# AdderRev1.net
KiCad netlist of a schematic drawn in EAGLE
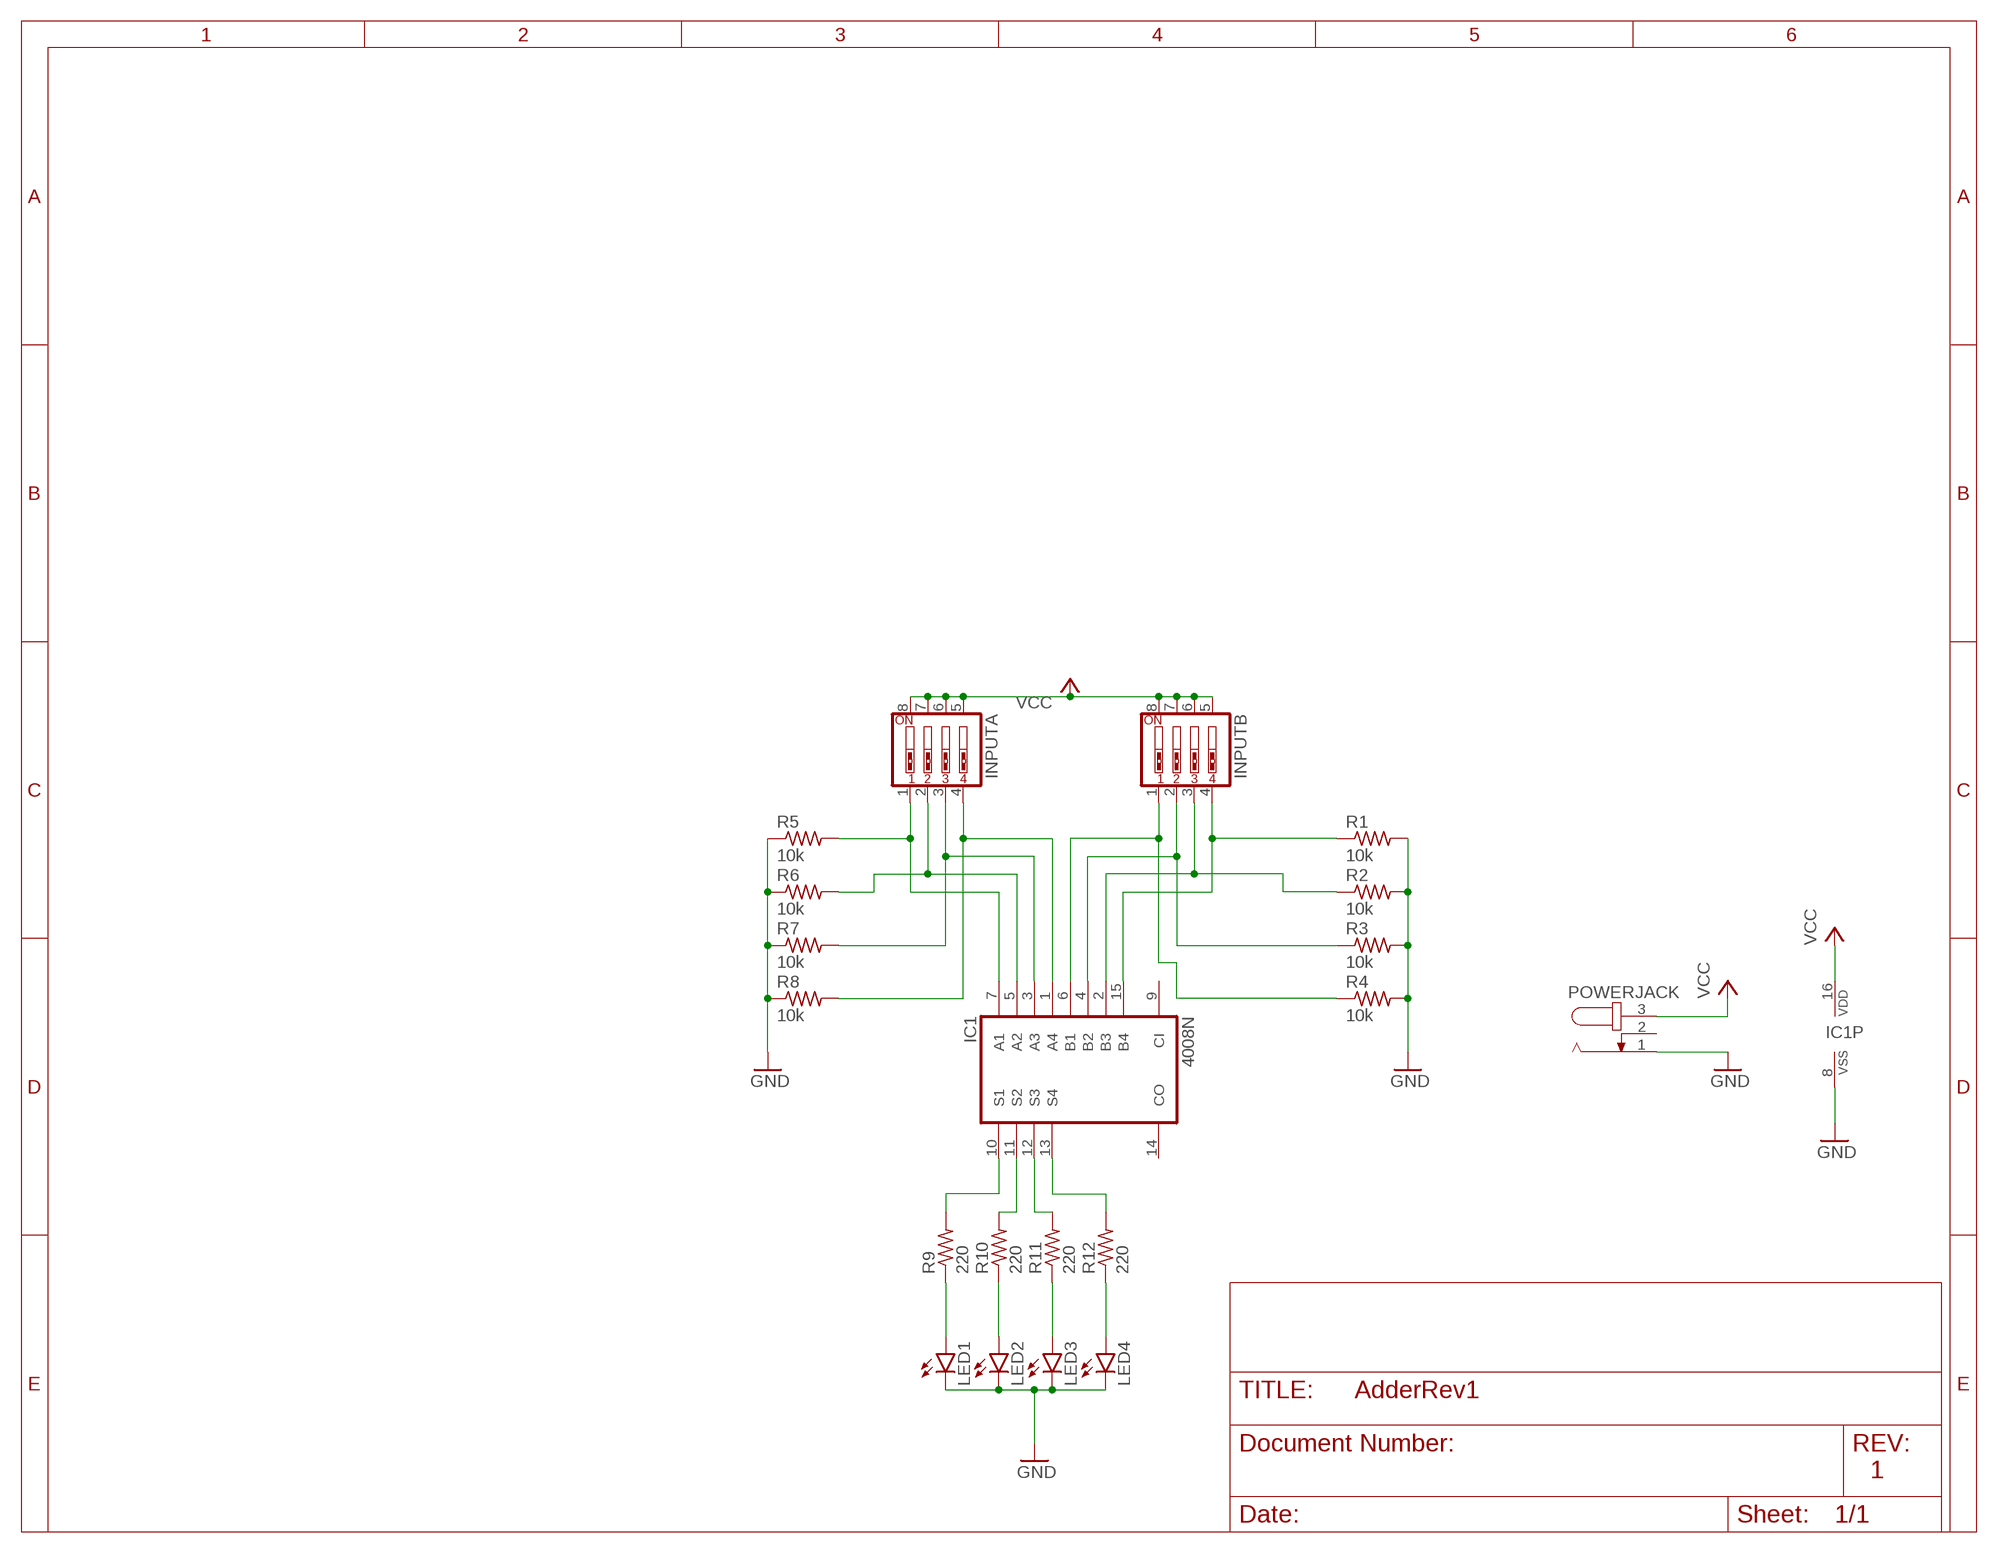
[diagram p0: schematic, sheet 1]

(export (version "E")
  (design (tool "Eeschema 10.0.6"))
  (components
    (comp (ref "IC1")
      (value "4008N")
      (footprint "eagle-import:DIL16")
      (libsource (lib "eagle-import") (part "4008N"))
    )
    (comp (ref "INPUTA")
      (value "SW_DIP-4")
      (footprint "eagle-import:EDG-04")
      (libsource (lib "eagle-import") (part "SW_DIP-4"))
    )
    (comp (ref "INPUTB")
      (value "SW_DIP-4")
      (footprint "eagle-import:EDG-04")
      (libsource (lib "eagle-import") (part "SW_DIP-4"))
    )
    (comp (ref "LED1")
      (value "LED5MM")
      (footprint "eagle-import:LED5MM")
      (libsource (lib "eagle-import") (part "LED5MM"))
    )
    (comp (ref "LED2")
      (value "LED5MM")
      (footprint "eagle-import:LED5MM")
      (libsource (lib "eagle-import") (part "LED5MM"))
    )
    (comp (ref "LED3")
      (value "LED5MM")
      (footprint "eagle-import:LED5MM")
      (libsource (lib "eagle-import") (part "LED5MM"))
    )
    (comp (ref "LED4")
      (value "LED5MM")
      (footprint "eagle-import:LED5MM")
      (libsource (lib "eagle-import") (part "LED5MM"))
    )
    (comp (ref "POWERJACK")
      (value "JACK-PLUG1")
      (footprint "eagle-import:SPC4078")
      (libsource (lib "eagle-import") (part "JACK-PLUG1"))
    )
    (comp (ref "R1")
      (value "10k")
      (footprint "eagle-import:0204_7")
      (libsource (lib "eagle-import") (part "R-US_0204/7"))
    )
    (comp (ref "R2")
      (value "10k")
      (footprint "eagle-import:0204_7")
      (libsource (lib "eagle-import") (part "R-US_0204/7"))
    )
    (comp (ref "R3")
      (value "10k")
      (footprint "eagle-import:0204_7")
      (libsource (lib "eagle-import") (part "R-US_0204/7"))
    )
    (comp (ref "R4")
      (value "10k")
      (footprint "eagle-import:0204_7")
      (libsource (lib "eagle-import") (part "R-US_0204/7"))
    )
    (comp (ref "R5")
      (value "10k")
      (footprint "eagle-import:0204_7")
      (libsource (lib "eagle-import") (part "R-US_0204/7"))
    )
    (comp (ref "R6")
      (value "10k")
      (footprint "eagle-import:0204_7")
      (libsource (lib "eagle-import") (part "R-US_0204/7"))
    )
    (comp (ref "R7")
      (value "10k")
      (footprint "eagle-import:0204_7")
      (libsource (lib "eagle-import") (part "R-US_0204/7"))
    )
    (comp (ref "R8")
      (value "10k")
      (footprint "eagle-import:0204_7")
      (libsource (lib "eagle-import") (part "R-US_0204/7"))
    )
    (comp (ref "R9")
      (value "220")
      (footprint "eagle-import:0204_7")
      (libsource (lib "eagle-import") (part "R-US_0204/7"))
    )
    (comp (ref "R10")
      (value "220")
      (footprint "eagle-import:0204_7")
      (libsource (lib "eagle-import") (part "R-US_0204/7"))
    )
    (comp (ref "R11")
      (value "220")
      (footprint "eagle-import:0204_7")
      (libsource (lib "eagle-import") (part "R-US_0204/7"))
    )
    (comp (ref "R12")
      (value "220")
      (footprint "eagle-import:0204_7")
      (libsource (lib "eagle-import") (part "R-US_0204/7"))
    )
  )
  (nets
    (net (code "1") (name "GND") (class "Default")
      (node (ref "IC1") (pin "8") (pinfunction "VSS_8") (pintype "power_in"))
      (node (ref "LED1") (pin "K") (pinfunction "C_K") (pintype "passive"))
      (node (ref "LED2") (pin "K") (pinfunction "C_K") (pintype "passive"))
      (node (ref "LED3") (pin "K") (pinfunction "C_K") (pintype "passive"))
      (node (ref "LED4") (pin "K") (pinfunction "C_K") (pintype "passive"))
      (node (ref "POWERJACK") (pin "1") (pinfunction "1_1") (pintype "passive"))
      (node (ref "R1") (pin "2") (pinfunction "2_2") (pintype "passive"))
      (node (ref "R2") (pin "2") (pinfunction "2_2") (pintype "passive"))
      (node (ref "R3") (pin "2") (pinfunction "2_2") (pintype "passive"))
      (node (ref "R4") (pin "2") (pinfunction "2_2") (pintype "passive"))
      (node (ref "R5") (pin "1") (pinfunction "1_1") (pintype "passive"))
      (node (ref "R6") (pin "1") (pinfunction "1_1") (pintype "passive"))
      (node (ref "R7") (pin "1") (pinfunction "1_1") (pintype "passive"))
      (node (ref "R8") (pin "1") (pinfunction "1_1") (pintype "passive"))
    )
    (net (code "2") (name "Net-(IC1A-A1)") (class "Default")
      (node (ref "IC1") (pin "7") (pinfunction "A1_7") (pintype "input"))
      (node (ref "INPUTA") (pin "1") (pinfunction "1_1") (pintype "passive"))
      (node (ref "R5") (pin "2") (pinfunction "2_2") (pintype "passive"))
    )
    (net (code "3") (name "Net-(IC1A-A2)") (class "Default")
      (node (ref "IC1") (pin "5") (pinfunction "A2_5") (pintype "input"))
      (node (ref "INPUTA") (pin "2") (pinfunction "2_2") (pintype "passive"))
      (node (ref "R6") (pin "2") (pinfunction "2_2") (pintype "passive"))
    )
    (net (code "4") (name "Net-(IC1A-A3)") (class "Default")
      (node (ref "IC1") (pin "3") (pinfunction "A3_3") (pintype "input"))
      (node (ref "INPUTA") (pin "3") (pinfunction "3_3") (pintype "passive"))
      (node (ref "R7") (pin "2") (pinfunction "2_2") (pintype "passive"))
    )
    (net (code "5") (name "Net-(IC1A-A4)") (class "Default")
      (node (ref "IC1") (pin "1") (pinfunction "A4_1") (pintype "input"))
      (node (ref "INPUTA") (pin "4") (pinfunction "4_4") (pintype "passive"))
      (node (ref "R8") (pin "2") (pinfunction "2_2") (pintype "passive"))
    )
    (net (code "6") (name "Net-(IC1A-B1)") (class "Default")
      (node (ref "IC1") (pin "6") (pinfunction "B1_6") (pintype "input"))
      (node (ref "INPUTB") (pin "1") (pinfunction "1_1") (pintype "passive"))
      (node (ref "R4") (pin "1") (pinfunction "1_1") (pintype "passive"))
    )
    (net (code "7") (name "Net-(IC1A-B2)") (class "Default")
      (node (ref "IC1") (pin "4") (pinfunction "B2_4") (pintype "input"))
      (node (ref "INPUTB") (pin "2") (pinfunction "2_2") (pintype "passive"))
      (node (ref "R3") (pin "1") (pinfunction "1_1") (pintype "passive"))
    )
    (net (code "8") (name "Net-(IC1A-B3)") (class "Default")
      (node (ref "IC1") (pin "2") (pinfunction "B3_2") (pintype "input"))
      (node (ref "INPUTB") (pin "3") (pinfunction "3_3") (pintype "passive"))
      (node (ref "R2") (pin "1") (pinfunction "1_1") (pintype "passive"))
    )
    (net (code "9") (name "Net-(IC1A-B4)") (class "Default")
      (node (ref "IC1") (pin "15") (pinfunction "B4_15") (pintype "input"))
      (node (ref "INPUTB") (pin "4") (pinfunction "4_4") (pintype "passive"))
      (node (ref "R1") (pin "1") (pinfunction "1_1") (pintype "passive"))
    )
    (net (code "10") (name "Net-(IC1A-S1)") (class "Default")
      (node (ref "IC1") (pin "10") (pinfunction "S1_10") (pintype "output"))
      (node (ref "R9") (pin "2") (pinfunction "2_2") (pintype "passive"))
    )
    (net (code "11") (name "Net-(IC1A-S2)") (class "Default")
      (node (ref "IC1") (pin "11") (pinfunction "S2_11") (pintype "output"))
      (node (ref "R10") (pin "2") (pinfunction "2_2") (pintype "passive"))
    )
    (net (code "12") (name "Net-(IC1A-S3)") (class "Default")
      (node (ref "IC1") (pin "12") (pinfunction "S3_12") (pintype "output"))
      (node (ref "R11") (pin "2") (pinfunction "2_2") (pintype "passive"))
    )
    (net (code "13") (name "Net-(IC1A-S4)") (class "Default")
      (node (ref "IC1") (pin "13") (pinfunction "S4_13") (pintype "output"))
      (node (ref "R12") (pin "2") (pinfunction "2_2") (pintype "passive"))
    )
    (net (code "14") (name "Net-(LED1-PadA)") (class "Default")
      (node (ref "LED1") (pin "A") (pinfunction "A_A") (pintype "passive"))
      (node (ref "R9") (pin "1") (pinfunction "1_1") (pintype "passive"))
    )
    (net (code "15") (name "Net-(LED2-PadA)") (class "Default")
      (node (ref "LED2") (pin "A") (pinfunction "A_A") (pintype "passive"))
      (node (ref "R10") (pin "1") (pinfunction "1_1") (pintype "passive"))
    )
    (net (code "16") (name "Net-(LED3-PadA)") (class "Default")
      (node (ref "LED3") (pin "A") (pinfunction "A_A") (pintype "passive"))
      (node (ref "R11") (pin "1") (pinfunction "1_1") (pintype "passive"))
    )
    (net (code "17") (name "Net-(LED4-PadA)") (class "Default")
      (node (ref "LED4") (pin "A") (pinfunction "A_A") (pintype "passive"))
      (node (ref "R12") (pin "1") (pinfunction "1_1") (pintype "passive"))
    )
    (net (code "18") (name "VCC") (class "Default")
      (node (ref "IC1") (pin "16") (pinfunction "VDD_16") (pintype "power_in"))
      (node (ref "INPUTA") (pin "5") (pinfunction "5_5") (pintype "passive"))
      (node (ref "INPUTA") (pin "6") (pinfunction "6_6") (pintype "passive"))
      (node (ref "INPUTA") (pin "7") (pinfunction "7_7") (pintype "passive"))
      (node (ref "INPUTA") (pin "8") (pinfunction "8_8") (pintype "passive"))
      (node (ref "INPUTB") (pin "5") (pinfunction "5_5") (pintype "passive"))
      (node (ref "INPUTB") (pin "6") (pinfunction "6_6") (pintype "passive"))
      (node (ref "INPUTB") (pin "7") (pinfunction "7_7") (pintype "passive"))
      (node (ref "INPUTB") (pin "8") (pinfunction "8_8") (pintype "passive"))
      (node (ref "POWERJACK") (pin "3") (pinfunction "3_3") (pintype "passive"))
    )
    (net (code "19") (name "unconnected-(IC1A-CI-Pad9)") (class "Default")
      (node (ref "IC1") (pin "9") (pinfunction "CI_9") (pintype "input"))
    )
    (net (code "20") (name "unconnected-(IC1A-CO-Pad14)") (class "Default")
      (node (ref "IC1") (pin "14") (pinfunction "CO_14") (pintype "output"))
    )
    (net (code "21") (name "unconnected-(POWERJACK-Pad2)") (class "Default")
      (node (ref "POWERJACK") (pin "2") (pinfunction "2_2") (pintype "passive"))
    )
  )
)
